# ATEM-Tally-SDI.net
KiCad netlist of a schematic drawn in EAGLE
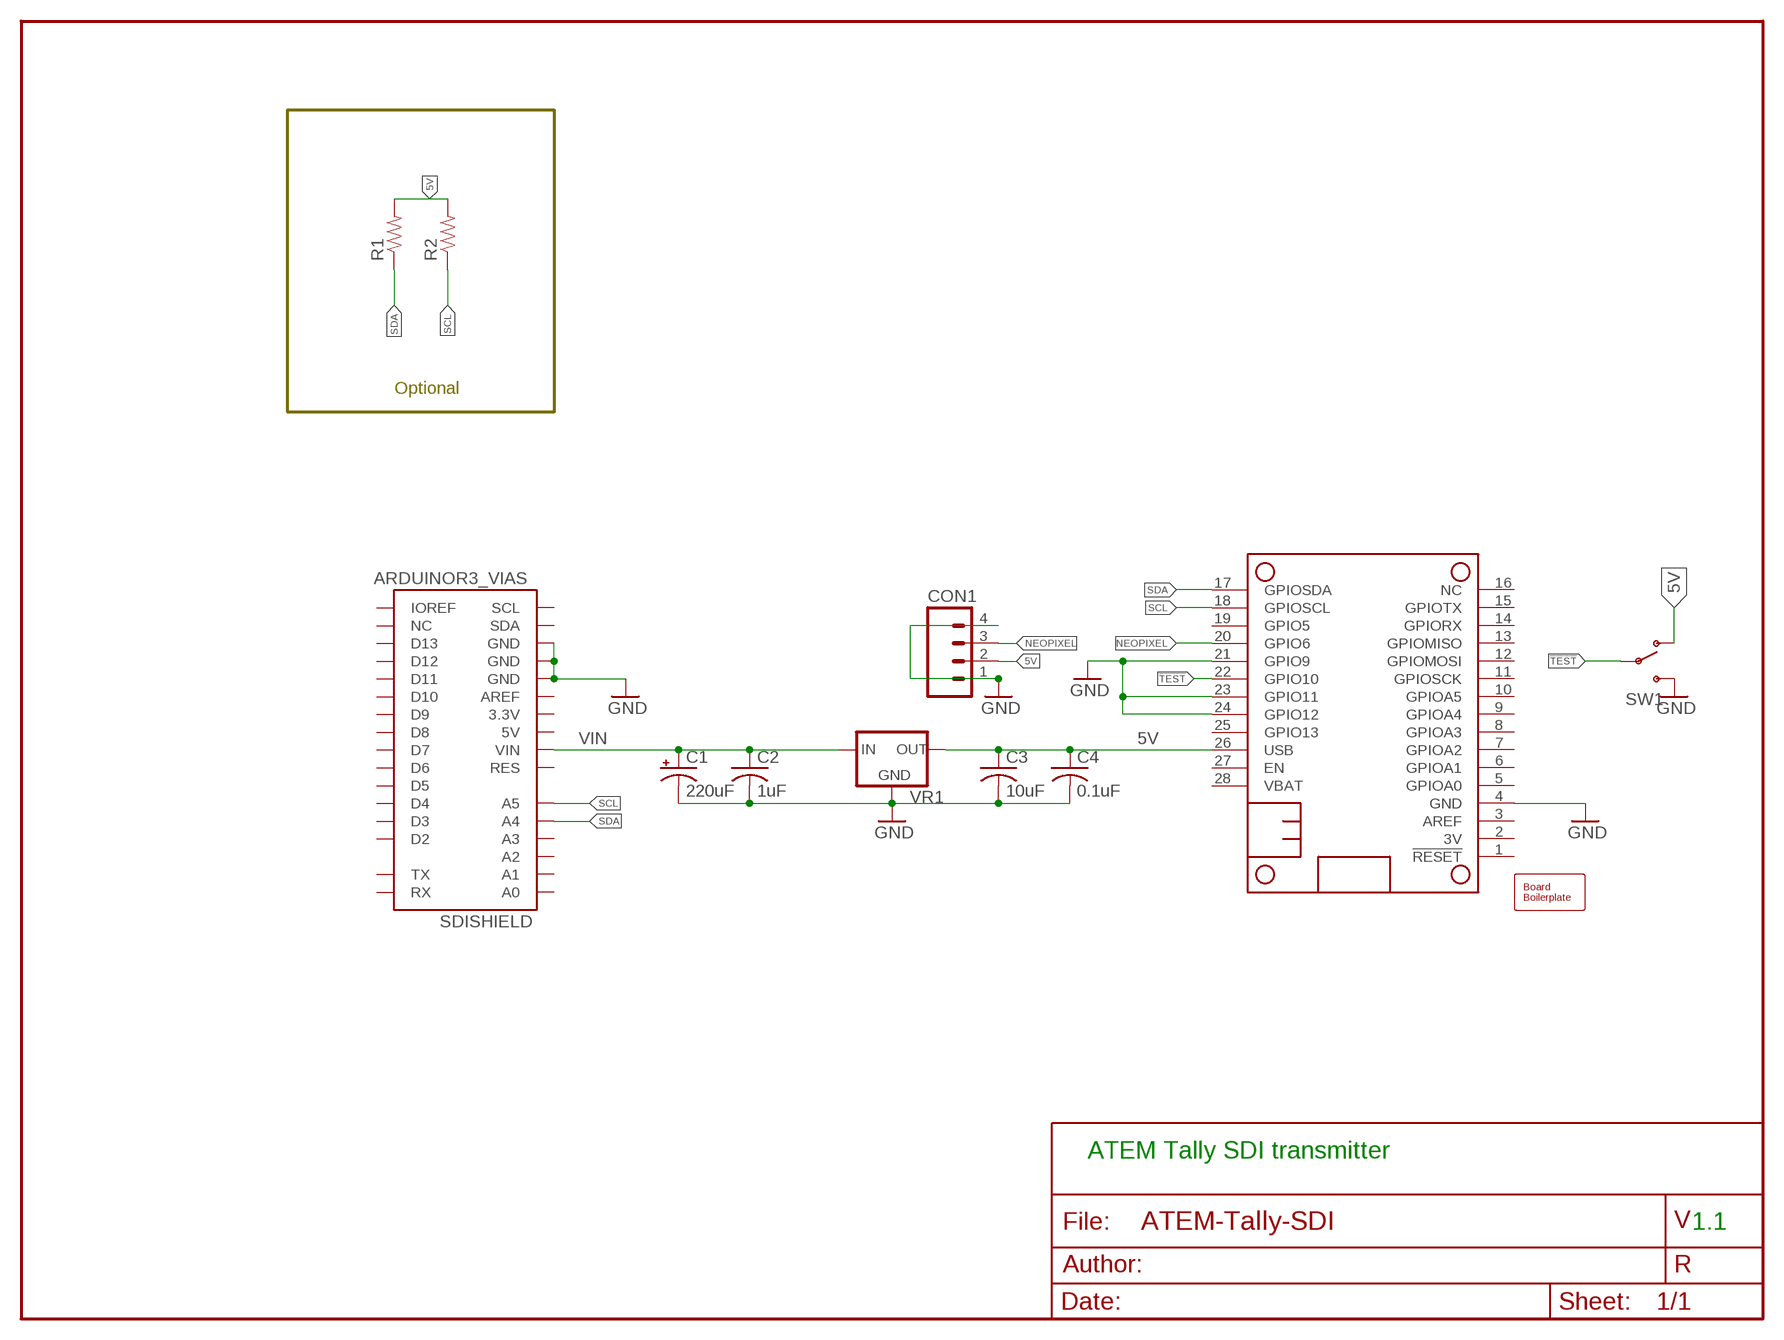
[diagram p0: schematic, sheet 1]

(export (version "E")
  (design (tool "Eeschema 10.0.6"))
  (components
    (comp (ref "BOARD1")
      (value "BOARD80X100")
      (footprint "eagle-import:BOARD-DINRAIL-3.17INX10CM")
      (libsource (lib "eagle-import") (part "BOARD80X100"))
    )
    (comp (ref "C1")
      (value "220uF")
      (footprint "eagle-import:0810-CAP")
      (libsource (lib "eagle-import") (part "CAP-POL0810"))
    )
    (comp (ref "C2")
      (value "1uF")
      (footprint "eagle-import:0603-CAP")
      (libsource (lib "eagle-import") (part "CAP0603"))
    )
    (comp (ref "C3")
      (value "10uF")
      (footprint "eagle-import:0603-CAP")
      (libsource (lib "eagle-import") (part "CAP0603"))
    )
    (comp (ref "C4")
      (value "0.1uF")
      (footprint "eagle-import:0603-CAP")
      (libsource (lib "eagle-import") (part "CAP0603"))
    )
    (comp (ref "CON1")
      (value "CONNECTOR-M04LOCK")
      (footprint "eagle-import:1X04_LOCK")
      (libsource (lib "eagle-import") (part "CONNECTOR-M04LOCK"))
    )
    (comp (ref "FEATHER")
      (value "FEATHERWING_NODIM")
      (footprint "eagle-import:FEATHERWING_DIM")
      (libsource (lib "eagle-import") (part "FEATHERWING_NODIM"))
    )
    (comp (ref "R1")
      (value "RPTH04")
      (footprint "eagle-import:AXIAL-0.4-RES")
      (libsource (lib "eagle-import") (part "RPTH04"))
    )
    (comp (ref "R2")
      (value "RPTH04")
      (footprint "eagle-import:AXIAL-0.4-RES")
      (libsource (lib "eagle-import") (part "RPTH04"))
    )
    (comp (ref "SDISHIELD")
      (value "ARDUINOR3_VIAS")
      (footprint "eagle-import:ARDUINO_R3_VIAS")
      (libsource (lib "eagle-import") (part "ARDUINOR3_VIAS"))
    )
    (comp (ref "SW1")
      (value "SWITCH-SPSTPTH")
      (footprint "eagle-import:SWITCH-SPDT")
      (libsource (lib "eagle-import") (part "SWITCH-SPSTPTH"))
    )
    (comp (ref "VR1")
      (value "VREG-DPAK-5")
      (footprint "eagle-import:TO-252")
      (libsource (lib "eagle-import") (part "VREG-?-DPAK5"))
    )
  )
  (nets
    (net (code "1") (name "/3V") (class "Default")
      (node (ref "FEATHER") (pin "2") (pinfunction "3V_2") (pintype "power_in"))
    )
    (net (code "2") (name "/VBAT") (class "Default")
      (node (ref "FEATHER") (pin "28") (pinfunction "VBAT_28") (pintype "power_in"))
    )
    (net (code "3") (name "/VIN") (class "Default")
      (node (ref "C1") (pin "+") (pinfunction "+_+") (pintype "passive"))
      (node (ref "C2") (pin "1") (pinfunction "1_1") (pintype "passive"))
      (node (ref "SDISHIELD") (pin "VIN") (pinfunction "VIN_VIN") (pintype "bidirectional"))
      (node (ref "VR1") (pin "1") (pinfunction "IN_1") (pintype "input"))
    )
    (net (code "4") (name "/~{TEST}") (class "Default")
      (node (ref "FEATHER") (pin "22") (pinfunction "GPIO10_22") (pintype "bidirectional"))
      (node (ref "SW1") (pin "2") (pinfunction "P_2") (pintype "passive"))
    )
    (net (code "5") (name "5V") (class "Default")
      (node (ref "C3") (pin "1") (pinfunction "1_1") (pintype "passive"))
      (node (ref "C4") (pin "1") (pinfunction "1_1") (pintype "passive"))
      (node (ref "CON1") (pin "2") (pinfunction "2_2") (pintype "passive"))
      (node (ref "FEATHER") (pin "26") (pinfunction "USB_26") (pintype "power_in"))
      (node (ref "R1") (pin "P$2") (pinfunction "2_P$2") (pintype "passive"))
      (node (ref "R2") (pin "P$2") (pinfunction "2_P$2") (pintype "passive"))
      (node (ref "SW1") (pin "1") (pinfunction "O_1") (pintype "passive"))
      (node (ref "VR1") (pin "3") (pinfunction "OUT_3") (pintype "output"))
    )
    (net (code "6") (name "GND") (class "Default")
      (node (ref "C1") (pin "-") (pinfunction "-_-") (pintype "passive"))
      (node (ref "C2") (pin "2") (pinfunction "2_2") (pintype "passive"))
      (node (ref "C3") (pin "2") (pinfunction "2_2") (pintype "passive"))
      (node (ref "C4") (pin "2") (pinfunction "2_2") (pintype "passive"))
      (node (ref "CON1") (pin "1") (pinfunction "1_1") (pintype "passive"))
      (node (ref "CON1") (pin "4") (pinfunction "4_4") (pintype "passive"))
      (node (ref "FEATHER") (pin "21") (pinfunction "GPIO9_21") (pintype "bidirectional"))
      (node (ref "FEATHER") (pin "23") (pinfunction "GPIO11_23") (pintype "bidirectional"))
      (node (ref "FEATHER") (pin "24") (pinfunction "GPIO12_24") (pintype "bidirectional"))
      (node (ref "FEATHER") (pin "4") (pinfunction "GND_4") (pintype "power_in"))
      (node (ref "SDISHIELD") (pin "GND@0") (pinfunction "GND_GND@0") (pintype "bidirectional"))
      (node (ref "SDISHIELD") (pin "GND@1") (pinfunction "GND_GND@1") (pintype "bidirectional"))
      (node (ref "SDISHIELD") (pin "GND@2") (pinfunction "GND_GND@2") (pintype "bidirectional"))
      (node (ref "SW1") (pin "3") (pinfunction "S_3") (pintype "passive"))
      (node (ref "VR1") (pin "2") (pinfunction "GND_2") (pintype "input"))
    )
    (net (code "7") (name "NEOPIXEL") (class "Default")
      (node (ref "CON1") (pin "3") (pinfunction "3_3") (pintype "passive"))
      (node (ref "FEATHER") (pin "20") (pinfunction "GPIO6_20") (pintype "bidirectional"))
    )
    (net (code "8") (name "SCL") (class "Default")
      (node (ref "FEATHER") (pin "18") (pinfunction "GPIOSCL_18") (pintype "bidirectional"))
      (node (ref "R2") (pin "P$1") (pinfunction "1_P$1") (pintype "passive"))
      (node (ref "SDISHIELD") (pin "A5") (pinfunction "A5_A5") (pintype "bidirectional"))
    )
    (net (code "9") (name "SDA") (class "Default")
      (node (ref "FEATHER") (pin "17") (pinfunction "GPIOSDA_17") (pintype "bidirectional"))
      (node (ref "R1") (pin "P$1") (pinfunction "1_P$1") (pintype "passive"))
      (node (ref "SDISHIELD") (pin "A4") (pinfunction "A4_A4") (pintype "bidirectional"))
    )
    (net (code "10") (name "unconnected-(FEATHER-AREF-Pad3)") (class "Default")
      (node (ref "FEATHER") (pin "3") (pinfunction "AREF_3") (pintype "passive"))
    )
    (net (code "11") (name "unconnected-(FEATHER-EN-Pad27)") (class "Default")
      (node (ref "FEATHER") (pin "27") (pinfunction "EN_27") (pintype "passive"))
    )
    (net (code "12") (name "unconnected-(FEATHER-GPIO5-Pad19)") (class "Default")
      (node (ref "FEATHER") (pin "19") (pinfunction "GPIO5_19") (pintype "bidirectional"))
    )
    (net (code "13") (name "unconnected-(FEATHER-GPIO13-Pad25)") (class "Default")
      (node (ref "FEATHER") (pin "25") (pinfunction "GPIO13_25") (pintype "bidirectional"))
    )
    (net (code "14") (name "unconnected-(FEATHER-GPIOA0-Pad5)") (class "Default")
      (node (ref "FEATHER") (pin "5") (pinfunction "GPIOA0_5") (pintype "bidirectional"))
    )
    (net (code "15") (name "unconnected-(FEATHER-GPIOA1-Pad6)") (class "Default")
      (node (ref "FEATHER") (pin "6") (pinfunction "GPIOA1_6") (pintype "bidirectional"))
    )
    (net (code "16") (name "unconnected-(FEATHER-GPIOA2-Pad7)") (class "Default")
      (node (ref "FEATHER") (pin "7") (pinfunction "GPIOA2_7") (pintype "bidirectional"))
    )
    (net (code "17") (name "unconnected-(FEATHER-GPIOA3-Pad8)") (class "Default")
      (node (ref "FEATHER") (pin "8") (pinfunction "GPIOA3_8") (pintype "bidirectional"))
    )
    (net (code "18") (name "unconnected-(FEATHER-GPIOA4-Pad9)") (class "Default")
      (node (ref "FEATHER") (pin "9") (pinfunction "GPIOA4_9") (pintype "bidirectional"))
    )
    (net (code "19") (name "unconnected-(FEATHER-GPIOA5-Pad10)") (class "Default")
      (node (ref "FEATHER") (pin "10") (pinfunction "GPIOA5_10") (pintype "bidirectional"))
    )
    (net (code "20") (name "unconnected-(FEATHER-GPIOMISO-Pad13)") (class "Default")
      (node (ref "FEATHER") (pin "13") (pinfunction "GPIOMISO_13") (pintype "bidirectional"))
    )
    (net (code "21") (name "unconnected-(FEATHER-GPIOMOSI-Pad12)") (class "Default")
      (node (ref "FEATHER") (pin "12") (pinfunction "GPIOMOSI_12") (pintype "bidirectional"))
    )
    (net (code "22") (name "unconnected-(FEATHER-GPIORX-Pad14)") (class "Default")
      (node (ref "FEATHER") (pin "14") (pinfunction "GPIORX_14") (pintype "bidirectional"))
    )
    (net (code "23") (name "unconnected-(FEATHER-GPIOSCK-Pad11)") (class "Default")
      (node (ref "FEATHER") (pin "11") (pinfunction "GPIOSCK_11") (pintype "bidirectional"))
    )
    (net (code "24") (name "unconnected-(FEATHER-GPIOTX-Pad15)") (class "Default")
      (node (ref "FEATHER") (pin "15") (pinfunction "GPIOTX_15") (pintype "bidirectional"))
    )
    (net (code "25") (name "unconnected-(FEATHER-NC-Pad16)") (class "Default")
      (node (ref "FEATHER") (pin "16") (pinfunction "NC_16") (pintype "passive"))
    )
    (net (code "26") (name "unconnected-(FEATHER-~{RESET}-Pad1)") (class "Default")
      (node (ref "FEATHER") (pin "1") (pinfunction "~{RESET}_1") (pintype "input"))
    )
    (net (code "27") (name "unconnected-(SDISHIELD-NC-PadNC1)") (class "Default")
      (node (ref "SDISHIELD") (pin "NC1") (pinfunction "NC_NC1") (pintype "bidirectional"))
    )
    (net (code "28") (name "unconnected-(SDISHIELD-Pad3.3V)") (class "Default")
      (node (ref "SDISHIELD") (pin "3.3V") (pinfunction "3.3V_3.3V") (pintype "bidirectional"))
    )
    (net (code "29") (name "unconnected-(SDISHIELD-Pad5V)") (class "Default")
      (node (ref "SDISHIELD") (pin "5V") (pinfunction "5V_5V") (pintype "bidirectional"))
    )
    (net (code "30") (name "unconnected-(SDISHIELD-PadA0)") (class "Default")
      (node (ref "SDISHIELD") (pin "A0") (pinfunction "A0_A0") (pintype "bidirectional"))
    )
    (net (code "31") (name "unconnected-(SDISHIELD-PadA1)") (class "Default")
      (node (ref "SDISHIELD") (pin "A1") (pinfunction "A1_A1") (pintype "bidirectional"))
    )
    (net (code "32") (name "unconnected-(SDISHIELD-PadA2)") (class "Default")
      (node (ref "SDISHIELD") (pin "A2") (pinfunction "A2_A2") (pintype "bidirectional"))
    )
    (net (code "33") (name "unconnected-(SDISHIELD-PadA3)") (class "Default")
      (node (ref "SDISHIELD") (pin "A3") (pinfunction "A3_A3") (pintype "bidirectional"))
    )
    (net (code "34") (name "unconnected-(SDISHIELD-PadAREF)") (class "Default")
      (node (ref "SDISHIELD") (pin "AREF") (pinfunction "AREF_AREF") (pintype "bidirectional"))
    )
    (net (code "35") (name "unconnected-(SDISHIELD-PadD2)") (class "Default")
      (node (ref "SDISHIELD") (pin "D2") (pinfunction "D2_D2") (pintype "bidirectional"))
    )
    (net (code "36") (name "unconnected-(SDISHIELD-PadD3)") (class "Default")
      (node (ref "SDISHIELD") (pin "D3") (pinfunction "D3_D3") (pintype "bidirectional"))
    )
    (net (code "37") (name "unconnected-(SDISHIELD-PadD4)") (class "Default")
      (node (ref "SDISHIELD") (pin "D4") (pinfunction "D4_D4") (pintype "bidirectional"))
    )
    (net (code "38") (name "unconnected-(SDISHIELD-PadD5)") (class "Default")
      (node (ref "SDISHIELD") (pin "D5") (pinfunction "D5_D5") (pintype "bidirectional"))
    )
    (net (code "39") (name "unconnected-(SDISHIELD-PadD6)") (class "Default")
      (node (ref "SDISHIELD") (pin "D6") (pinfunction "D6_D6") (pintype "bidirectional"))
    )
    (net (code "40") (name "unconnected-(SDISHIELD-PadD7)") (class "Default")
      (node (ref "SDISHIELD") (pin "D7") (pinfunction "D7_D7") (pintype "bidirectional"))
    )
    (net (code "41") (name "unconnected-(SDISHIELD-PadD8)") (class "Default")
      (node (ref "SDISHIELD") (pin "D8") (pinfunction "D8_D8") (pintype "bidirectional"))
    )
    (net (code "42") (name "unconnected-(SDISHIELD-PadD9)") (class "Default")
      (node (ref "SDISHIELD") (pin "D9") (pinfunction "D9_D9") (pintype "bidirectional"))
    )
    (net (code "43") (name "unconnected-(SDISHIELD-PadD10)") (class "Default")
      (node (ref "SDISHIELD") (pin "D10") (pinfunction "D10_D10") (pintype "bidirectional"))
    )
    (net (code "44") (name "unconnected-(SDISHIELD-PadD11)") (class "Default")
      (node (ref "SDISHIELD") (pin "D11") (pinfunction "D11_D11") (pintype "bidirectional"))
    )
    (net (code "45") (name "unconnected-(SDISHIELD-PadD12)") (class "Default")
      (node (ref "SDISHIELD") (pin "D12") (pinfunction "D12_D12") (pintype "bidirectional"))
    )
    (net (code "46") (name "unconnected-(SDISHIELD-PadD13)") (class "Default")
      (node (ref "SDISHIELD") (pin "D13") (pinfunction "D13_D13") (pintype "bidirectional"))
    )
    (net (code "47") (name "unconnected-(SDISHIELD-PadIOREF)") (class "Default")
      (node (ref "SDISHIELD") (pin "IOREF") (pinfunction "IOREF_IOREF") (pintype "bidirectional"))
    )
    (net (code "48") (name "unconnected-(SDISHIELD-PadRES)") (class "Default")
      (node (ref "SDISHIELD") (pin "RES") (pinfunction "RES_RES") (pintype "bidirectional"))
    )
    (net (code "49") (name "unconnected-(SDISHIELD-PadRX)") (class "Default")
      (node (ref "SDISHIELD") (pin "RX") (pinfunction "RX_RX") (pintype "bidirectional"))
    )
    (net (code "50") (name "unconnected-(SDISHIELD-PadSCL)") (class "Default")
      (node (ref "SDISHIELD") (pin "SCL") (pinfunction "SCL_SCL") (pintype "bidirectional"))
    )
    (net (code "51") (name "unconnected-(SDISHIELD-PadSDA)") (class "Default")
      (node (ref "SDISHIELD") (pin "SDA") (pinfunction "SDA_SDA") (pintype "bidirectional"))
    )
    (net (code "52") (name "unconnected-(SDISHIELD-PadTX)") (class "Default")
      (node (ref "SDISHIELD") (pin "TX") (pinfunction "TX_TX") (pintype "bidirectional"))
    )
  )
)
